# relays.net
KiCad netlist of a schematic drawn in EAGLE
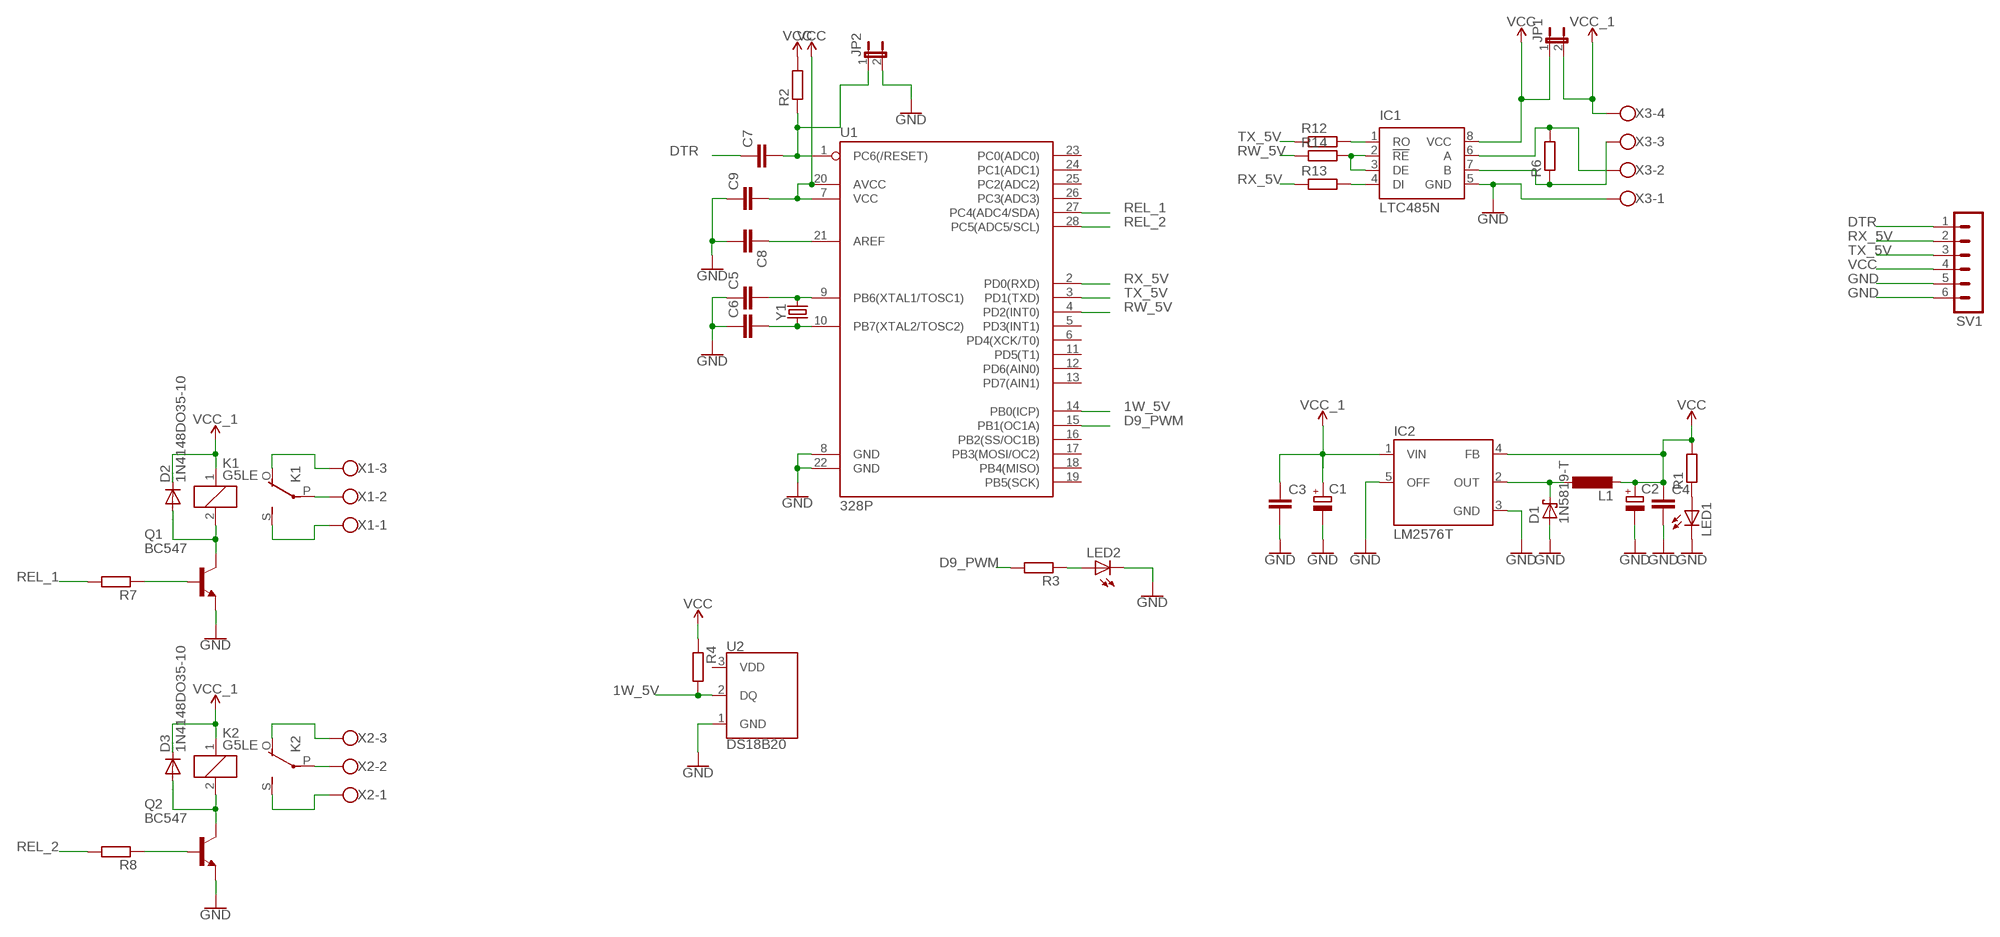
[diagram p0: schematic, sheet 1]

(export (version "E")
  (design (tool "Eeschema 10.0.6"))
  (components
    (comp (ref "C1")
      (value "CPOL-EUE5-10.5")
      (footprint "eagle-import:E5-10,5")
      (libsource (lib "eagle-import") (part "CPOL-EUE5-10.5"))
    )
    (comp (ref "C2")
      (value "CPOL-EUE5-10.5")
      (footprint "eagle-import:E5-10,5")
      (libsource (lib "eagle-import") (part "CPOL-EUE5-10.5"))
    )
    (comp (ref "C3")
      (value "C-EU025-025X050")
      (footprint "eagle-import:C025-025X050")
      (libsource (lib "eagle-import") (part "C-EU025-025X050"))
    )
    (comp (ref "C4")
      (value "C-EU025-025X050")
      (footprint "eagle-import:C025-025X050")
      (libsource (lib "eagle-import") (part "C-EU025-025X050"))
    )
    (comp (ref "C5")
      (value "C-EU025-025X050")
      (footprint "eagle-import:C025-025X050")
      (libsource (lib "eagle-import") (part "C-EU025-025X050"))
    )
    (comp (ref "C6")
      (value "C-EU025-025X050")
      (footprint "eagle-import:C025-025X050")
      (libsource (lib "eagle-import") (part "C-EU025-025X050"))
    )
    (comp (ref "C7")
      (value "C-EU025-025X050")
      (footprint "eagle-import:C025-025X050")
      (libsource (lib "eagle-import") (part "C-EU025-025X050"))
    )
    (comp (ref "C8")
      (value "C-EU025-025X050")
      (footprint "eagle-import:C025-025X050")
      (libsource (lib "eagle-import") (part "C-EU025-025X050"))
    )
    (comp (ref "C9")
      (value "C-EU025-025X050")
      (footprint "eagle-import:C025-025X050")
      (libsource (lib "eagle-import") (part "C-EU025-025X050"))
    )
    (comp (ref "D1")
      (value "1N5819-T")
      (footprint "eagle-import:DO41-7.6")
      (libsource (lib "eagle-import") (part "1N5819-T"))
    )
    (comp (ref "D2")
      (value "1N4148DO35-10")
      (footprint "eagle-import:DO35-10")
      (libsource (lib "eagle-import") (part "1N4148DO35-10"))
    )
    (comp (ref "D3")
      (value "1N4148DO35-10")
      (footprint "eagle-import:DO35-10")
      (libsource (lib "eagle-import") (part "1N4148DO35-10"))
    )
    (comp (ref "IC1")
      (value "LTC485N")
      (footprint "eagle-import:DIL08")
      (libsource (lib "eagle-import") (part "LTC485N"))
    )
    (comp (ref "IC2")
      (value "LM2576T")
      (footprint "eagle-import:TO220-5")
      (libsource (lib "eagle-import") (part "LM2576T"))
    )
    (comp (ref "JP1")
      (value "JP1E")
      (footprint "eagle-import:JP1")
      (libsource (lib "eagle-import") (part "JP1E"))
    )
    (comp (ref "JP2")
      (value "JP1E")
      (footprint "eagle-import:JP1")
      (libsource (lib "eagle-import") (part "JP1E"))
    )
    (comp (ref "K1")
      (value "G5LE")
      (footprint "eagle-import:G5LE")
      (libsource (lib "eagle-import") (part "G5LE"))
    )
    (comp (ref "K2")
      (value "G5LE")
      (footprint "eagle-import:G5LE")
      (libsource (lib "eagle-import") (part "G5LE"))
    )
    (comp (ref "L1")
      (value "L-EUTJ3-U1")
      (footprint "eagle-import:TJ3-U1")
      (libsource (lib "eagle-import") (part "L-EUTJ3-U1"))
    )
    (comp (ref "LED1")
      (value "LED5MM")
      (footprint "eagle-import:LED5MM")
      (libsource (lib "eagle-import") (part "LED5MM"))
    )
    (comp (ref "LED2")
      (value "LED5MM")
      (footprint "eagle-import:LED5MM")
      (libsource (lib "eagle-import") (part "LED5MM"))
    )
    (comp (ref "Q1")
      (value "BC547")
      (footprint "eagle-import:TO92")
      (libsource (lib "eagle-import") (part "BC547"))
    )
    (comp (ref "Q2")
      (value "BC547")
      (footprint "eagle-import:TO92")
      (libsource (lib "eagle-import") (part "BC547"))
    )
    (comp (ref "R1")
      (value "R-EU_0204/7")
      (footprint "eagle-import:0204_7")
      (libsource (lib "eagle-import") (part "R-EU_0204/7"))
    )
    (comp (ref "R2")
      (value "R-EU_0204/7")
      (footprint "eagle-import:0204_7")
      (libsource (lib "eagle-import") (part "R-EU_0204/7"))
    )
    (comp (ref "R3")
      (value "R-EU_0204/7")
      (footprint "eagle-import:0204_7")
      (libsource (lib "eagle-import") (part "R-EU_0204/7"))
    )
    (comp (ref "R4")
      (value "R-EU_0204/7")
      (footprint "eagle-import:0204_7")
      (libsource (lib "eagle-import") (part "R-EU_0204/7"))
    )
    (comp (ref "R6")
      (value "R-EU_0204/7")
      (footprint "eagle-import:0204_7")
      (libsource (lib "eagle-import") (part "R-EU_0204/7"))
    )
    (comp (ref "R7")
      (value "R-EU_0204/7")
      (footprint "eagle-import:0204_7")
      (libsource (lib "eagle-import") (part "R-EU_0204/7"))
    )
    (comp (ref "R8")
      (value "R-EU_0204/7")
      (footprint "eagle-import:0204_7")
      (libsource (lib "eagle-import") (part "R-EU_0204/7"))
    )
    (comp (ref "R12")
      (value "R-EU_0204/7")
      (footprint "eagle-import:0204_7")
      (libsource (lib "eagle-import") (part "R-EU_0204/7"))
    )
    (comp (ref "R13")
      (value "R-EU_0204/7")
      (footprint "eagle-import:0204_7")
      (libsource (lib "eagle-import") (part "R-EU_0204/7"))
    )
    (comp (ref "R14")
      (value "R-EU_0204/7")
      (footprint "eagle-import:0204_7")
      (libsource (lib "eagle-import") (part "R-EU_0204/7"))
    )
    (comp (ref "SV1")
      (value "MA06-1")
      (footprint "eagle-import:MA06-1")
      (libsource (lib "eagle-import") (part "MA06-1"))
    )
    (comp (ref "U1")
      (value "328P")
      (footprint "eagle-import:DIP28")
      (libsource (lib "eagle-import") (part "ATMEGA328P_PDIP"))
    )
    (comp (ref "U2")
      (value "DS18B20")
      (footprint "eagle-import:TO-92-AMMO")
      (libsource (lib "eagle-import") (part "DS18B20"))
    )
    (comp (ref "X1")
      (value "W237-103")
      (footprint "eagle-import:W237-103")
      (fields (field (name "MPN") "237-103"))
      (libsource (lib "eagle-import") (part "W237-103"))
    )
    (comp (ref "X2")
      (value "W237-103")
      (footprint "eagle-import:W237-103")
      (fields (field (name "MPN") "237-103"))
      (libsource (lib "eagle-import") (part "W237-103"))
    )
    (comp (ref "X3")
      (value "W237-4")
      (footprint "eagle-import:W237-4")
      (libsource (lib "eagle-import") (part "W237-4"))
    )
    (comp (ref "Y1")
      (value "CRYSTALPTH-HC49US")
      (footprint "eagle-import:HC49US")
      (libsource (lib "eagle-import") (part "CRYSTALPTH-HC49US"))
    )
  )
  (nets
    (net (code "1") (name "/1W_5V") (class "Default")
      (node (ref "R4") (pin "2") (pinfunction "2_2") (pintype "passive"))
      (node (ref "U1") (pin "14") (pinfunction "PB0(ICP)_14") (pintype "bidirectional"))
      (node (ref "U2") (pin "2") (pinfunction "DQ_2") (pintype "bidirectional"))
    )
    (net (code "2") (name "/D9_PWM") (class "Default")
      (node (ref "R3") (pin "2") (pinfunction "2_2") (pintype "passive"))
      (node (ref "U1") (pin "15") (pinfunction "PB1(OC1A)_15") (pintype "bidirectional"))
    )
    (net (code "3") (name "/DTR") (class "Default")
      (node (ref "C7") (pin "1") (pinfunction "1_1") (pintype "passive"))
      (node (ref "SV1") (pin "1") (pinfunction "1_1") (pintype "passive"))
    )
    (net (code "4") (name "/REL_1") (class "Default")
      (node (ref "R7") (pin "2") (pinfunction "2_2") (pintype "passive"))
      (node (ref "U1") (pin "27") (pinfunction "PC4(ADC4/SDA)_27") (pintype "bidirectional"))
    )
    (net (code "5") (name "/REL_2") (class "Default")
      (node (ref "R8") (pin "2") (pinfunction "2_2") (pintype "passive"))
      (node (ref "U1") (pin "28") (pinfunction "PC5(ADC5/SCL)_28") (pintype "bidirectional"))
    )
    (net (code "6") (name "/RW_5V") (class "Default")
      (node (ref "R14") (pin "1") (pinfunction "1_1") (pintype "passive"))
      (node (ref "U1") (pin "4") (pinfunction "PD2(INT0)_4") (pintype "bidirectional"))
    )
    (net (code "7") (name "/RX_5V") (class "Default")
      (node (ref "R13") (pin "1") (pinfunction "1_1") (pintype "passive"))
      (node (ref "SV1") (pin "2") (pinfunction "2_2") (pintype "passive"))
      (node (ref "U1") (pin "2") (pinfunction "PD0(RXD)_2") (pintype "bidirectional"))
    )
    (net (code "8") (name "/TX_5V") (class "Default")
      (node (ref "R12") (pin "1") (pinfunction "1_1") (pintype "passive"))
      (node (ref "SV1") (pin "3") (pinfunction "3_3") (pintype "passive"))
      (node (ref "U1") (pin "3") (pinfunction "PD1(TXD)_3") (pintype "bidirectional"))
    )
    (net (code "9") (name "/VDD") (class "Default")
      (node (ref "U2") (pin "3") (pinfunction "VDD_3") (pintype "power_in"))
    )
    (net (code "10") (name "GND") (class "Default")
      (node (ref "C1") (pin "-") (pinfunction "-_-") (pintype "passive"))
      (node (ref "C2") (pin "-") (pinfunction "-_-") (pintype "passive"))
      (node (ref "C3") (pin "2") (pinfunction "2_2") (pintype "passive"))
      (node (ref "C4") (pin "2") (pinfunction "2_2") (pintype "passive"))
      (node (ref "C5") (pin "1") (pinfunction "1_1") (pintype "passive"))
      (node (ref "C6") (pin "1") (pinfunction "1_1") (pintype "passive"))
      (node (ref "C8") (pin "2") (pinfunction "2_2") (pintype "passive"))
      (node (ref "C9") (pin "1") (pinfunction "1_1") (pintype "passive"))
      (node (ref "D1") (pin "A") (pinfunction "A_A") (pintype "passive"))
      (node (ref "IC1") (pin "5") (pinfunction "GND_5") (pintype "input"))
      (node (ref "IC2") (pin "3") (pinfunction "GND_3") (pintype "power_in"))
      (node (ref "IC2") (pin "5") (pinfunction "OFF_5") (pintype "input"))
      (node (ref "JP2") (pin "2") (pinfunction "2_2") (pintype "passive"))
      (node (ref "LED1") (pin "K") (pinfunction "C_K") (pintype "passive"))
      (node (ref "LED2") (pin "K") (pinfunction "C_K") (pintype "passive"))
      (node (ref "Q1") (pin "1") (pinfunction "E_1") (pintype "passive"))
      (node (ref "Q2") (pin "1") (pinfunction "E_1") (pintype "passive"))
      (node (ref "SV1") (pin "5") (pinfunction "5_5") (pintype "passive"))
      (node (ref "SV1") (pin "6") (pinfunction "6_6") (pintype "passive"))
      (node (ref "U1") (pin "22") (pinfunction "GND_22") (pintype "bidirectional"))
      (node (ref "U1") (pin "8") (pinfunction "GND_8") (pintype "bidirectional"))
      (node (ref "U2") (pin "1") (pinfunction "GND_1") (pintype "power_in"))
      (node (ref "X3") (pin "1") (pinfunction "KL_1") (pintype "passive"))
    )
    (net (code "11") (name "Net-(IC1-A)") (class "Default")
      (node (ref "IC1") (pin "6") (pinfunction "A_6") (pintype "bidirectional"))
      (node (ref "R6") (pin "2") (pinfunction "2_2") (pintype "passive"))
      (node (ref "X3") (pin "2") (pinfunction "KL_2") (pintype "passive"))
    )
    (net (code "12") (name "Net-(IC1-B)") (class "Default")
      (node (ref "IC1") (pin "7") (pinfunction "B_7") (pintype "bidirectional"))
      (node (ref "R6") (pin "1") (pinfunction "1_1") (pintype "passive"))
      (node (ref "X3") (pin "3") (pinfunction "KL_3") (pintype "passive"))
    )
    (net (code "13") (name "Net-(IC1-DE)") (class "Default")
      (node (ref "IC1") (pin "2") (pinfunction "~{RE}_2") (pintype "input"))
      (node (ref "IC1") (pin "3") (pinfunction "DE_3") (pintype "input"))
      (node (ref "R14") (pin "2") (pinfunction "2_2") (pintype "passive"))
    )
    (net (code "14") (name "Net-(IC1-DI)") (class "Default")
      (node (ref "IC1") (pin "4") (pinfunction "DI_4") (pintype "input"))
      (node (ref "R13") (pin "2") (pinfunction "2_2") (pintype "passive"))
    )
    (net (code "15") (name "Net-(IC1-RO)") (class "Default")
      (node (ref "IC1") (pin "1") (pinfunction "RO_1") (pintype "output"))
      (node (ref "R12") (pin "2") (pinfunction "2_2") (pintype "passive"))
    )
    (net (code "16") (name "Net-(IC2-OUT)") (class "Default")
      (node (ref "D1") (pin "C") (pinfunction "C_C") (pintype "passive"))
      (node (ref "IC2") (pin "2") (pinfunction "OUT_2") (pintype "output"))
      (node (ref "L1") (pin "1") (pinfunction "1_1") (pintype "passive"))
    )
    (net (code "17") (name "Net-(LED1-PadA)") (class "Default")
      (node (ref "LED1") (pin "A") (pinfunction "A_A") (pintype "passive"))
      (node (ref "R1") (pin "1") (pinfunction "1_1") (pintype "passive"))
    )
    (net (code "18") (name "Net-(LED2-PadA)") (class "Default")
      (node (ref "LED2") (pin "A") (pinfunction "A_A") (pintype "passive"))
      (node (ref "R3") (pin "1") (pinfunction "1_1") (pintype "passive"))
    )
    (net (code "19") (name "Net-(Q1-B)") (class "Default")
      (node (ref "Q1") (pin "2") (pinfunction "B_2") (pintype "passive"))
      (node (ref "R7") (pin "1") (pinfunction "1_1") (pintype "passive"))
    )
    (net (code "20") (name "Net-(Q1-C)") (class "Default")
      (node (ref "D2") (pin "A") (pinfunction "A_A") (pintype "passive"))
      (node (ref "K1") (pin "2") (pinfunction "2_2") (pintype "passive"))
      (node (ref "Q1") (pin "3") (pinfunction "C_3") (pintype "passive"))
    )
    (net (code "21") (name "Net-(Q2-B)") (class "Default")
      (node (ref "Q2") (pin "2") (pinfunction "B_2") (pintype "passive"))
      (node (ref "R8") (pin "1") (pinfunction "1_1") (pintype "passive"))
    )
    (net (code "22") (name "Net-(Q2-C)") (class "Default")
      (node (ref "D3") (pin "A") (pinfunction "A_A") (pintype "passive"))
      (node (ref "K2") (pin "2") (pinfunction "2_2") (pintype "passive"))
      (node (ref "Q2") (pin "3") (pinfunction "C_3") (pintype "passive"))
    )
    (net (code "23") (name "Net-(U1-AREF)") (class "Default")
      (node (ref "C8") (pin "1") (pinfunction "1_1") (pintype "passive"))
      (node (ref "U1") (pin "21") (pinfunction "AREF_21") (pintype "bidirectional"))
    )
    (net (code "24") (name "Net-(U1-PB6(XTAL1{slash}TOSC1))") (class "Default")
      (node (ref "C5") (pin "2") (pinfunction "2_2") (pintype "passive"))
      (node (ref "U1") (pin "9") (pinfunction "PB6(XTAL1/TOSC1)_9") (pintype "bidirectional"))
      (node (ref "Y1") (pin "2") (pinfunction "2_2") (pintype "passive"))
    )
    (net (code "25") (name "Net-(U1-PB7(XTAL2{slash}TOSC2))") (class "Default")
      (node (ref "C6") (pin "2") (pinfunction "2_2") (pintype "passive"))
      (node (ref "U1") (pin "10") (pinfunction "PB7(XTAL2/TOSC2)_10") (pintype "bidirectional"))
      (node (ref "Y1") (pin "1") (pinfunction "1_1") (pintype "passive"))
    )
    (net (code "26") (name "Net-(U1-PC6({slash}RESET))") (class "Default")
      (node (ref "C7") (pin "2") (pinfunction "2_2") (pintype "passive"))
      (node (ref "JP2") (pin "1") (pinfunction "1_1") (pintype "passive"))
      (node (ref "R2") (pin "1") (pinfunction "1_1") (pintype "passive"))
      (node (ref "U1") (pin "1") (pinfunction "PC6(/RESET)_1") (pintype "bidirectional"))
    )
    (net (code "27") (name "Net-(X1A-KL)") (class "Default")
      (node (ref "K1") (pin "S") (pinfunction "S_S") (pintype "passive"))
      (node (ref "X1") (pin "1") (pinfunction "KL_1") (pintype "passive"))
    )
    (net (code "28") (name "Net-(X1B-KL)") (class "Default")
      (node (ref "K1") (pin "P") (pinfunction "P_P") (pintype "passive"))
      (node (ref "X1") (pin "2") (pinfunction "KL_2") (pintype "passive"))
    )
    (net (code "29") (name "Net-(X1C-KL)") (class "Default")
      (node (ref "K1") (pin "O") (pinfunction "O_O") (pintype "passive"))
      (node (ref "X1") (pin "3") (pinfunction "KL_3") (pintype "passive"))
    )
    (net (code "30") (name "Net-(X2A-KL)") (class "Default")
      (node (ref "K2") (pin "S") (pinfunction "S_S") (pintype "passive"))
      (node (ref "X2") (pin "1") (pinfunction "KL_1") (pintype "passive"))
    )
    (net (code "31") (name "Net-(X2B-KL)") (class "Default")
      (node (ref "K2") (pin "P") (pinfunction "P_P") (pintype "passive"))
      (node (ref "X2") (pin "2") (pinfunction "KL_2") (pintype "passive"))
    )
    (net (code "32") (name "Net-(X2C-KL)") (class "Default")
      (node (ref "K2") (pin "O") (pinfunction "O_O") (pintype "passive"))
      (node (ref "X2") (pin "3") (pinfunction "KL_3") (pintype "passive"))
    )
    (net (code "33") (name "VCC") (class "Default")
      (node (ref "C2") (pin "+") (pinfunction "+_+") (pintype "passive"))
      (node (ref "C4") (pin "1") (pinfunction "1_1") (pintype "passive"))
      (node (ref "C9") (pin "2") (pinfunction "2_2") (pintype "passive"))
      (node (ref "IC1") (pin "8") (pinfunction "VCC_8") (pintype "input"))
      (node (ref "IC2") (pin "4") (pinfunction "FB_4") (pintype "input"))
      (node (ref "JP1") (pin "1") (pinfunction "1_1") (pintype "passive"))
      (node (ref "L1") (pin "2") (pinfunction "2_2") (pintype "passive"))
      (node (ref "R1") (pin "2") (pinfunction "2_2") (pintype "passive"))
      (node (ref "R2") (pin "2") (pinfunction "2_2") (pintype "passive"))
      (node (ref "R4") (pin "1") (pinfunction "1_1") (pintype "passive"))
      (node (ref "SV1") (pin "4") (pinfunction "4_4") (pintype "passive"))
      (node (ref "U1") (pin "20") (pinfunction "AVCC_20") (pintype "bidirectional"))
      (node (ref "U1") (pin "7") (pinfunction "VCC_7") (pintype "bidirectional"))
    )
    (net (code "34") (name "VCC_1") (class "Default")
      (node (ref "C1") (pin "+") (pinfunction "+_+") (pintype "passive"))
      (node (ref "C3") (pin "1") (pinfunction "1_1") (pintype "passive"))
      (node (ref "D2") (pin "C") (pinfunction "C_C") (pintype "passive"))
      (node (ref "D3") (pin "C") (pinfunction "C_C") (pintype "passive"))
      (node (ref "IC2") (pin "1") (pinfunction "VIN_1") (pintype "power_in"))
      (node (ref "JP1") (pin "2") (pinfunction "2_2") (pintype "passive"))
      (node (ref "K1") (pin "1") (pinfunction "1_1") (pintype "passive"))
      (node (ref "K2") (pin "1") (pinfunction "1_1") (pintype "passive"))
      (node (ref "X3") (pin "4") (pinfunction "KL_4") (pintype "passive"))
    )
    (net (code "35") (name "unconnected-(U1-PB2(SS{slash}OC1B)-Pad16)") (class "Default")
      (node (ref "U1") (pin "16") (pinfunction "PB2(SS/OC1B)_16") (pintype "bidirectional"))
    )
    (net (code "36") (name "unconnected-(U1-PB3(MOSI{slash}OC2)-Pad17)") (class "Default")
      (node (ref "U1") (pin "17") (pinfunction "PB3(MOSI/OC2)_17") (pintype "bidirectional"))
    )
    (net (code "37") (name "unconnected-(U1-PB4(MISO)-Pad18)") (class "Default")
      (node (ref "U1") (pin "18") (pinfunction "PB4(MISO)_18") (pintype "bidirectional"))
    )
    (net (code "38") (name "unconnected-(U1-PB5(SCK)-Pad19)") (class "Default")
      (node (ref "U1") (pin "19") (pinfunction "PB5(SCK)_19") (pintype "bidirectional"))
    )
    (net (code "39") (name "unconnected-(U1-PC0(ADC0)-Pad23)") (class "Default")
      (node (ref "U1") (pin "23") (pinfunction "PC0(ADC0)_23") (pintype "bidirectional"))
    )
    (net (code "40") (name "unconnected-(U1-PC1(ADC1)-Pad24)") (class "Default")
      (node (ref "U1") (pin "24") (pinfunction "PC1(ADC1)_24") (pintype "bidirectional"))
    )
    (net (code "41") (name "unconnected-(U1-PC2(ADC2)-Pad25)") (class "Default")
      (node (ref "U1") (pin "25") (pinfunction "PC2(ADC2)_25") (pintype "bidirectional"))
    )
    (net (code "42") (name "unconnected-(U1-PC3(ADC3)-Pad26)") (class "Default")
      (node (ref "U1") (pin "26") (pinfunction "PC3(ADC3)_26") (pintype "bidirectional"))
    )
    (net (code "43") (name "unconnected-(U1-PD3(INT1)-Pad5)") (class "Default")
      (node (ref "U1") (pin "5") (pinfunction "PD3(INT1)_5") (pintype "bidirectional"))
    )
    (net (code "44") (name "unconnected-(U1-PD4(XCK{slash}T0)-Pad6)") (class "Default")
      (node (ref "U1") (pin "6") (pinfunction "PD4(XCK/T0)_6") (pintype "bidirectional"))
    )
    (net (code "45") (name "unconnected-(U1-PD5(T1)-Pad11)") (class "Default")
      (node (ref "U1") (pin "11") (pinfunction "PD5(T1)_11") (pintype "bidirectional"))
    )
    (net (code "46") (name "unconnected-(U1-PD6(AIN0)-Pad12)") (class "Default")
      (node (ref "U1") (pin "12") (pinfunction "PD6(AIN0)_12") (pintype "bidirectional"))
    )
    (net (code "47") (name "unconnected-(U1-PD7(AIN1)-Pad13)") (class "Default")
      (node (ref "U1") (pin "13") (pinfunction "PD7(AIN1)_13") (pintype "bidirectional"))
    )
  )
)
